# 01_HMS_Power.net
KiCad netlist of a schematic drawn in Altium Designer
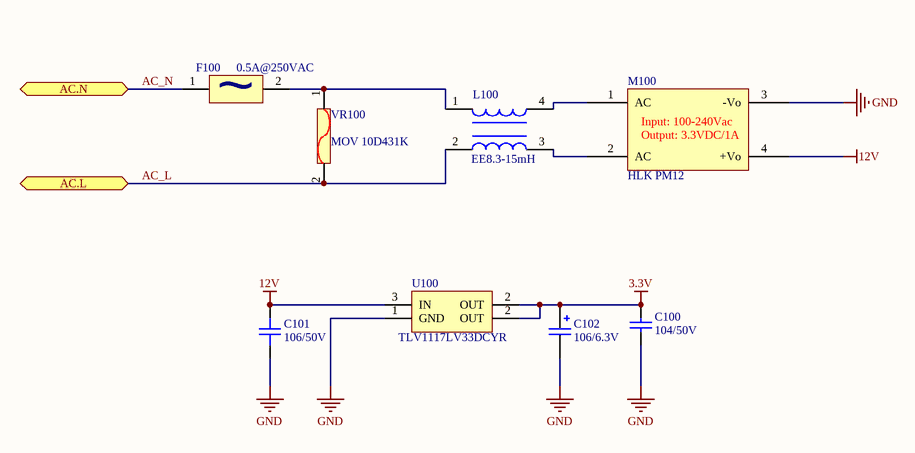
[diagram p0: [01].HMS.Power.SchDoc]

(export (version "E")
  (design (tool "Eeschema 10.0.6"))
  (components
    (comp (ref "C100")
      (value "104/50V")
      (footprint "CAP_CERAMIC_0402(1005)")
      (description "CAP CER 0.1UF 50V X5R 0402")
      (fields
        (field (name "MPN") "CC0402KRX5R9BB104")
        (field (name "MFR") "YAGEO")
        (field (name "PUBLISHER") "Altium Limited")
      )
      (libsource (lib "Miscellaneous Devices") (part "Cap"))
    )
    (comp (ref "C101")
      (value "106/50V")
      (footprint "CAP_CERAMIC_1206(3216-18)")
      (description "CAP Ceramic 106/16V 10% 1206")
      (fields (field (name "MPN") "CL31A106KOHNNNE"))
      (libsource (lib "01.Passives") (part "CL21A106KOQNNNE"))
    )
    (comp (ref "C102")
      (value "106/6.3V")
      (footprint "CAP_TANTAL_1206(3216-18)")
      (description "CAP Tantal 10uF/6.3V 10% 1206")
      (fields (field (name "MFR") "Nichicon") (field (name "MPN") "293D106X96R3A2TE3"))
      (libsource (lib "01.Capacitor") (part "UWT1C221MCL1GS"))
    )
    (comp (ref "F100")
      (value "0.5A@250VAC")
      (footprint "RUEF250U-2")
      (description "Cầu chì tự phục hồi 0.5A 250V")
      (fields
        (field (name "MANUFACTURER") "Bourns")
        (field (name "MANUFACTURER PART NUMBER") "MF-RX250/72-2")
      )
      (libsource (lib "20.OtherPassive") (part "RUEF250U-2"))
    )
    (comp (ref "L100")
      (value "EE8.3-15mH")
      (footprint "EE8.3-15mH")
      (description "Cuộn lọc 15mH EE8.3")
      (libsource (lib "03.Inductor") (part "EE8.3-15mH"))
    )
    (comp (ref "M100")
      (value "HLK PM12")
      (footprint "HLK PW03")
      (description "Module Power AC Convertor DC 220VAC - 12VDC")
      (fields (field (name "MPN") "HLKPM03"))
      (libsource (lib "14.Module") (part "HLK PM03"))
    )
    (comp (ref "U100")
      (value "TLV1117LV33DCYR")
      (footprint "LM1117-SOP")
      (description "800mA and 1A Low Dropout Positive Regulator 3.3V")
      (fields (field (name "PUBLISHER") "Altium Limited"))
      (libsource (lib "BB Power Mgt Voltage Regulator") (part "REG1117-3.3"))
    )
    (comp (ref "VR100")
      (value "MOV 10D431K")
      (footprint "MOV 10D431K")
      (description "Varistor 10D431K 430V 10mm")
      (fields (field (name "MPN") "10D431K"))
      (libsource (lib "10.Miscellaneous") (part "Varistor 10D431K"))
    )
  )
  (nets
    (net (code "1") (name "/AC_L") (class "Default")
      (node (ref "L100") (pin "2") (pinfunction "2_2") (pintype "passive"))
      (node (ref "VR100") (pin "2") (pinfunction "41_2") (pintype "passive"))
    )
    (net (code "2") (name "/AC_N") (class "Default")
      (node (ref "F100") (pin "1") (pinfunction "1_1") (pintype "passive"))
    )
    (net (code "3") (name "3.3V") (class "Default")
      (node (ref "C100") (pin "2") (pinfunction "2_2") (pintype "passive"))
      (node (ref "C102") (pin "1") (pinfunction "1_1") (pintype "passive"))
      (node (ref "U100") (pin "2") (pinfunction "OUT_2") (pintype "passive"))
    )
    (net (code "4") (name "12V") (class "Default")
      (node (ref "C101") (pin "1") (pinfunction "1_1") (pintype "passive"))
      (node (ref "M100") (pin "4") (pinfunction "+Vo_4") (pintype "passive"))
      (node (ref "U100") (pin "3") (pinfunction "IN_3") (pintype "passive"))
    )
    (net (code "5") (name "GND") (class "Default")
      (node (ref "C100") (pin "1") (pinfunction "1_1") (pintype "passive"))
      (node (ref "C101") (pin "2") (pinfunction "2_2") (pintype "passive"))
      (node (ref "C102") (pin "2") (pinfunction "2_2") (pintype "passive"))
      (node (ref "M100") (pin "3") (pinfunction "-Vo_3") (pintype "passive"))
      (node (ref "U100") (pin "1") (pinfunction "GND_1") (pintype "passive"))
    )
    (net (code "6") (name "Net-(L100-Pad3)") (class "Default")
      (node (ref "L100") (pin "3") (pinfunction "3_3") (pintype "passive"))
      (node (ref "M100") (pin "2") (pinfunction "AC_2") (pintype "passive"))
    )
    (net (code "7") (name "Net-(L100-Pad4)") (class "Default")
      (node (ref "L100") (pin "4") (pinfunction "4_4") (pintype "passive"))
      (node (ref "M100") (pin "1") (pinfunction "AC_1") (pintype "passive"))
    )
    (net (code "8") (name "Net-(VR100-40)") (class "Default")
      (node (ref "F100") (pin "2") (pinfunction "2_2") (pintype "passive"))
      (node (ref "L100") (pin "1") (pinfunction "1_1") (pintype "passive"))
      (node (ref "VR100") (pin "1") (pinfunction "40_1") (pintype "passive"))
    )
  )
)
